# Breakout.net
KiCad netlist of a schematic drawn in Altium Designer
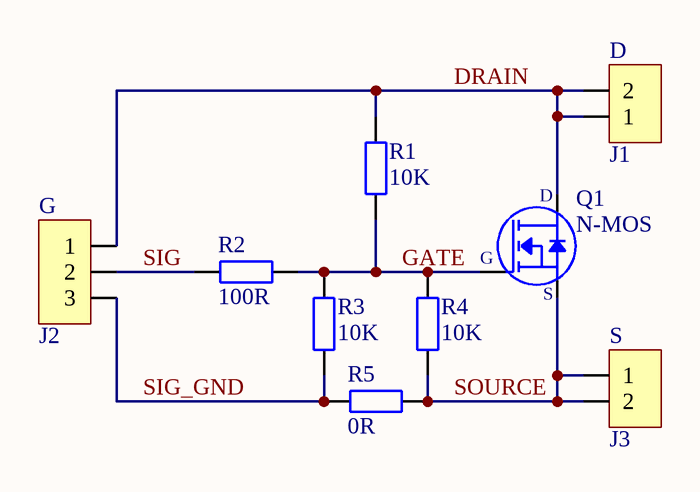
[diagram p0: Breakout.SchDoc]

(export (version "E")
  (design (tool "Eeschema 10.0.6"))
  (components
    (comp (ref "J1")
      (value "D")
      (footprint "HEADER-2.54-2P1")
      (description "Pin Header Single Row 2 Positions")
      (libsource (lib "AG.Connectors") (part "PINHDR-2P1"))
    )
    (comp (ref "J2")
      (value "G")
      (footprint "AG.Connectors:HEADER-2.54-3P1")
      (description "Generic Pin Header 3x1")
      (libsource (lib "AG.Connectors") (part "PINHDR-3P1"))
    )
    (comp (ref "J3")
      (value "S")
      (footprint "HEADER-2.54-2P1")
      (description "Pin Header Single Row 2 Positions")
      (libsource (lib "") (part "PINHDR-2P1_1"))
    )
    (comp (ref "Q1")
      (value "N-MOS")
      (footprint "IRLML_SOT-23")
      (description "MOSFET N-Channel")
      (fields (field (name "MANUFACTURER") "Generic Brand"))
      (libsource (lib "AG.Generic") (part "N-MOS"))
    )
    (comp (ref "R1")
      (value "10K")
      (footprint "0603R_RF_M")
      (description "Resistor")
      (fields (field (name "TOLERANCE") "?") (field (name "MANUFACTURER") "Generic Brand"))
      (libsource (lib "AG.Generic") (part "R"))
    )
    (comp (ref "R2")
      (value "100R")
      (footprint "0603R_RF_M")
      (description "Resistor")
      (fields (field (name "TOLERANCE") "?") (field (name "MANUFACTURER") "Generic Brand"))
      (libsource (lib "AG.Generic") (part "R"))
    )
    (comp (ref "R3")
      (value "10K")
      (footprint "0603R_RF_M")
      (description "Resistor")
      (fields (field (name "TOLERANCE") "?") (field (name "MANUFACTURER") "Generic Brand"))
      (libsource (lib "AG.Generic") (part "R"))
    )
    (comp (ref "R4")
      (value "10K")
      (footprint "0603R_RF_M")
      (description "Resistor")
      (fields (field (name "TOLERANCE") "?") (field (name "MANUFACTURER") "Generic Brand"))
      (libsource (lib "AG.Generic") (part "R"))
    )
    (comp (ref "R5")
      (value "0R")
      (footprint "0603R_RF_M")
      (description "Resistor")
      (fields (field (name "TOLERANCE") "?") (field (name "MANUFACTURER") "Generic Brand"))
      (libsource (lib "AG.Generic") (part "R"))
    )
  )
  (nets
    (net (code "1") (name "/DRAIN") (class "Default")
      (node (ref "J1") (pin "1") (pinfunction "1_1") (pintype "passive"))
      (node (ref "J1") (pin "2") (pinfunction "2_2") (pintype "passive"))
      (node (ref "J2") (pin "1") (pinfunction "1_1") (pintype "passive"))
      (node (ref "Q1") (pin "D") (pinfunction "Drain_D") (pintype "passive"))
      (node (ref "R1") (pin "1") (pintype "passive"))
    )
    (net (code "2") (name "/GATE") (class "Default")
      (node (ref "Q1") (pin "G") (pinfunction "Gate_G") (pintype "passive"))
      (node (ref "R1") (pin "2") (pintype "passive"))
      (node (ref "R2") (pin "2") (pintype "passive"))
      (node (ref "R3") (pin "1") (pintype "passive"))
      (node (ref "R4") (pin "1") (pintype "passive"))
    )
    (net (code "3") (name "/SIG") (class "Default")
      (node (ref "J2") (pin "2") (pinfunction "2_2") (pintype "passive"))
      (node (ref "R2") (pin "1") (pintype "passive"))
    )
    (net (code "4") (name "/SIG_GND") (class "Default")
      (node (ref "J2") (pin "3") (pinfunction "3_3") (pintype "passive"))
      (node (ref "R3") (pin "2") (pintype "passive"))
      (node (ref "R5") (pin "2") (pintype "passive"))
    )
    (net (code "5") (name "/SOURCE") (class "Default")
      (node (ref "J3") (pin "1") (pinfunction "1_1") (pintype "passive"))
      (node (ref "J3") (pin "2") (pinfunction "2_2") (pintype "passive"))
      (node (ref "Q1") (pin "S") (pinfunction "Source_S") (pintype "passive"))
      (node (ref "R4") (pin "2") (pintype "passive"))
      (node (ref "R5") (pin "1") (pintype "passive"))
    )
  )
)
